# GSM-Board.net
KiCad netlist of a schematic drawn in Altium Designer
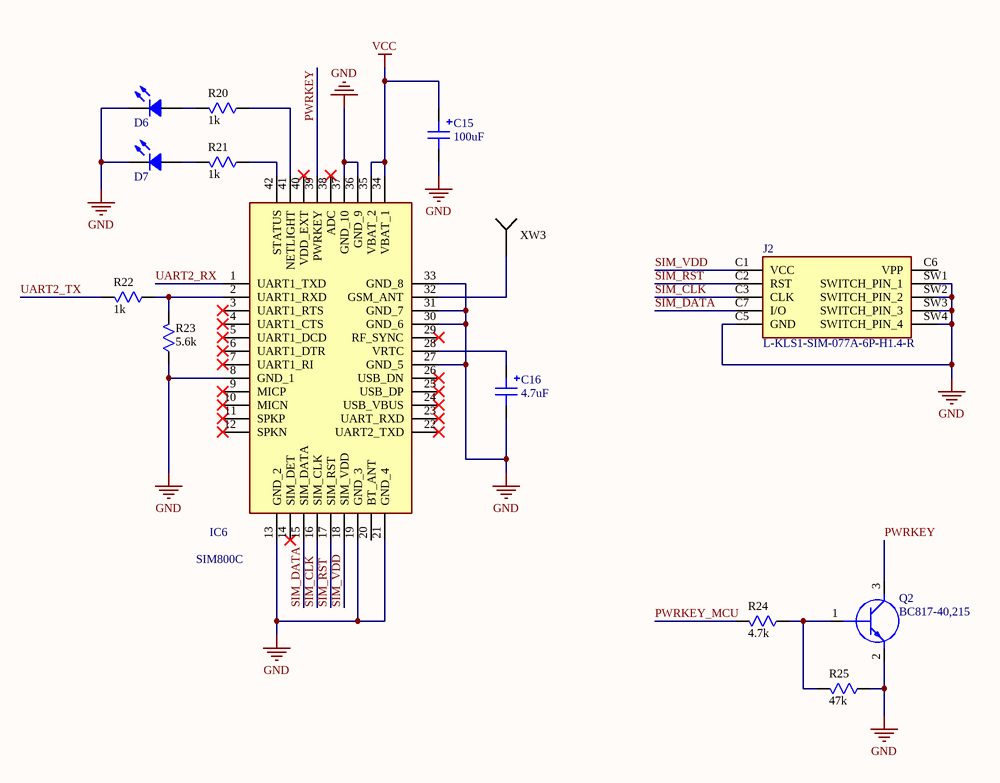
[diagram p0: GSM-Board.SchDoc]

(export (version "E")
  (design (tool "Eeschema 10.0.6"))
  (components
    (comp (ref "C15")
      (value "100uF")
      (footprint "PcbLib:CAP: TANTAL-D")
      (description "SMD Capacitor Polar")
      (libsource (lib "Schlib") (part "Capacitor_polar"))
    )
    (comp (ref "C16")
      (value "4.7uF")
      (footprint "PcbLib:CAP: TANTAL-A")
      (description "SMD Capacitor Polar")
      (libsource (lib "Schlib") (part "Capacitor_polar"))
    )
    (comp (ref "D6")
      (value "~")
      (footprint "PcbLib:LED0805")
      (description "Chip LED")
      (libsource (lib "Schlib") (part "LED"))
    )
    (comp (ref "D7")
      (value "~")
      (footprint "PcbLib:LED0805")
      (description "Chip LED")
      (libsource (lib "Schlib") (part "LED"))
    )
    (comp (ref "IC6")
      (value "SIM800C")
      (footprint "PcbLib:SIM800C")
      (description "Integrated Circuit")
      (fields (field (name "MANUFACTURER_PART_NUMBER") "-SIM800C"))
      (libsource (lib "Schlib") (part "-SIM800C"))
    )
    (comp (ref "J2")
      (value "L-KLS1-SIM-077A-6P-H1.4-R")
      (footprint "LKLS1SIM077A6PH14R")
      (description "Connector")
      (libsource (lib "Schlib") (part "L-KLS1-SIM-077A-6P-H1.4-R"))
    )
    (comp (ref "Q2")
      (value "BC817-40,215")
      (footprint "PcbLib:BC81740215")
      (description "Transistor BJT NPN")
      (fields (field (name "MOUSER PART NUMBER") "771-BC817-40-T/R"))
      (libsource (lib "*") (part "BC817-40,215"))
    )
    (comp (ref "R20")
      (value "1k")
      (footprint "PcbLib:RES: 0805")
      (fields
        (field (name "MANUFACTURER") "Yageo")
        (field (name "PARTNUMBER") "RC0201JR-07100RL")
        (field (name "VALUEMANUFACTURERPARTNUMBER") "Resistor film, 1k, , 0201, 0.05W, -55...+125°C")
      )
      (libsource (lib "Schlib") (part "Resistor"))
    )
    (comp (ref "R21")
      (value "1k")
      (footprint "PcbLib:RES: 0805")
      (fields
        (field (name "MANUFACTURER") "Yageo")
        (field (name "PARTNUMBER") "RC0201JR-07100RL")
        (field (name "VALUEMANUFACTURERPARTNUMBER") "Resistor film, 1k, , 0201, 0.05W, -55...+125°C")
      )
      (libsource (lib "Schlib") (part "Resistor"))
    )
    (comp (ref "R22")
      (value "1k")
      (footprint "PcbLib:RES: 0805")
      (fields
        (field (name "MANUFACTURER") "Yageo")
        (field (name "PARTNUMBER") "RC0201JR-07100RL")
        (field (name "VALUEMANUFACTURERPARTNUMBER") "Resistor film, 1k, , 0201, 0.05W, -55...+125°C")
      )
      (libsource (lib "Schlib") (part "Resistor"))
    )
    (comp (ref "R23")
      (value "5.6k")
      (footprint "PcbLib:RES: 0805")
      (fields
        (field (name "MANUFACTURER") "Yageo")
        (field (name "PARTNUMBER") "RC0201JR-07100RL")
        (field (name "VALUEMANUFACTURERPARTNUMBER") "Resistor film, 5.6k, , 0201, 0.05W, -55...+125°C")
      )
      (libsource (lib "Schlib") (part "Resistor"))
    )
    (comp (ref "R24")
      (value "4.7k")
      (footprint "PcbLib:RES: 0805")
      (fields
        (field (name "MANUFACTURER") "Yageo")
        (field (name "PARTNUMBER") "RC0201JR-07100RL")
        (field (name "VALUEMANUFACTURERPARTNUMBER") "Resistor film, 4.7k, , 0201, 0.05W, -55...+125°C")
      )
      (libsource (lib "Schlib") (part "Resistor"))
    )
    (comp (ref "R25")
      (value "47k")
      (footprint "PcbLib:RES: 0805")
      (fields
        (field (name "MANUFACTURER") "Yageo")
        (field (name "PARTNUMBER") "RC0201JR-07100RL")
        (field (name "VALUEMANUFACTURERPARTNUMBER") "Resistor film, 47k, , 0201, 0.05W, -55...+125°C")
      )
      (libsource (lib "Schlib") (part "Resistor"))
    )
    (comp (ref "XW3")
      (value "~")
      (footprint "CON: SMA EDGE MOUNT")
      (libsource (lib "Schlib") (part "Connector RF"))
    )
  )
  (nets
    (net (code "1") (name "/PWRKEY") (class "Default")
      (node (ref "IC6") (pin "39") (pinfunction "PWRKEY_39") (pintype "passive"))
      (node (ref "Q2") (pin "3") (pinfunction "C_3") (pintype "passive"))
    )
    (net (code "2") (name "/PWRKEY_MCU") (class "Default")
      (node (ref "R24") (pin "2") (pinfunction "2_2") (pintype "passive"))
    )
    (net (code "3") (name "/SIM_CLK") (class "Default")
      (node (ref "IC6") (pin "16") (pinfunction "SIM_CLK_16") (pintype "passive"))
      (node (ref "J2") (pin "C3") (pinfunction "CLK_C3") (pintype "passive"))
    )
    (net (code "4") (name "/SIM_DATA") (class "Default")
      (node (ref "IC6") (pin "15") (pinfunction "SIM_DATA_15") (pintype "passive"))
      (node (ref "J2") (pin "C7") (pinfunction "I/O_C7") (pintype "passive"))
    )
    (net (code "5") (name "/SIM_RST") (class "Default")
      (node (ref "IC6") (pin "17") (pinfunction "SIM_RST_17") (pintype "passive"))
      (node (ref "J2") (pin "C2") (pinfunction "RST_C2") (pintype "passive"))
    )
    (net (code "6") (name "/SIM_VDD") (class "Default")
      (node (ref "IC6") (pin "18") (pinfunction "SIM_VDD_18") (pintype "passive"))
      (node (ref "J2") (pin "C1") (pinfunction "VCC_C1") (pintype "passive"))
    )
    (net (code "7") (name "/UART2_RX") (class "Default")
      (node (ref "IC6") (pin "1") (pinfunction "UART1_TXD_1") (pintype "passive"))
    )
    (net (code "8") (name "/UART2_TX") (class "Default")
      (node (ref "R22") (pin "2") (pinfunction "2_2") (pintype "passive"))
    )
    (net (code "9") (name "GND") (class "Default")
      (node (ref "C15") (pin "2") (pinfunction "2_2") (pintype "passive"))
      (node (ref "C16") (pin "2") (pinfunction "2_2") (pintype "passive"))
      (node (ref "D6") (pin "2") (pinfunction "2_2") (pintype "passive"))
      (node (ref "D7") (pin "2") (pinfunction "2_2") (pintype "passive"))
      (node (ref "IC6") (pin "13") (pinfunction "GND_2_13") (pintype "passive"))
      (node (ref "IC6") (pin "19") (pinfunction "GND_3_19") (pintype "passive"))
      (node (ref "IC6") (pin "21") (pinfunction "GND_4_21") (pintype "passive"))
      (node (ref "IC6") (pin "27") (pinfunction "GND_5_27") (pintype "passive"))
      (node (ref "IC6") (pin "30") (pinfunction "GND_6_30") (pintype "passive"))
      (node (ref "IC6") (pin "31") (pinfunction "GND_7_31") (pintype "passive"))
      (node (ref "IC6") (pin "33") (pinfunction "GND_8_33") (pintype "passive"))
      (node (ref "IC6") (pin "36") (pinfunction "GND_9_36") (pintype "passive"))
      (node (ref "IC6") (pin "37") (pinfunction "GND_10_37") (pintype "passive"))
      (node (ref "IC6") (pin "8") (pinfunction "GND_1_8") (pintype "passive"))
      (node (ref "J2") (pin "C5") (pinfunction "GND_C5") (pintype "passive"))
      (node (ref "J2") (pin "SW1") (pinfunction "SWITCH_PIN_1_SW1") (pintype "passive"))
      (node (ref "J2") (pin "SW2") (pinfunction "SWITCH_PIN_2_SW2") (pintype "passive"))
      (node (ref "J2") (pin "SW3") (pinfunction "SWITCH_PIN_3_SW3") (pintype "passive"))
      (node (ref "J2") (pin "SW4") (pinfunction "SWITCH_PIN_4_SW4") (pintype "passive"))
      (node (ref "Q2") (pin "2") (pinfunction "E_2") (pintype "passive"))
      (node (ref "R23") (pin "1") (pinfunction "1_1") (pintype "passive"))
      (node (ref "R25") (pin "1") (pinfunction "1_1") (pintype "passive"))
    )
    (net (code "10") (name "Net-(D6-Pad1)") (class "Default")
      (node (ref "D6") (pin "1") (pinfunction "1_1") (pintype "passive"))
      (node (ref "R20") (pin "2") (pinfunction "2_2") (pintype "passive"))
    )
    (net (code "11") (name "Net-(D7-Pad1)") (class "Default")
      (node (ref "D7") (pin "1") (pinfunction "1_1") (pintype "passive"))
      (node (ref "R21") (pin "2") (pinfunction "2_2") (pintype "passive"))
    )
    (net (code "12") (name "Net-(IC6-GSM_ANT)") (class "Default")
      (node (ref "IC6") (pin "32") (pinfunction "GSM_ANT_32") (pintype "passive"))
      (node (ref "XW3") (pin "1") (pinfunction "SIG_1") (pintype "passive"))
    )
    (net (code "13") (name "Net-(IC6-NETLIGHT)") (class "Default")
      (node (ref "IC6") (pin "41") (pinfunction "NETLIGHT_41") (pintype "passive"))
      (node (ref "R20") (pin "1") (pinfunction "1_1") (pintype "passive"))
    )
    (net (code "14") (name "Net-(IC6-STATUS)") (class "Default")
      (node (ref "IC6") (pin "42") (pinfunction "STATUS_42") (pintype "passive"))
      (node (ref "R21") (pin "1") (pinfunction "1_1") (pintype "passive"))
    )
    (net (code "15") (name "Net-(IC6-UART1_RXD)") (class "Default")
      (node (ref "IC6") (pin "2") (pinfunction "UART1_RXD_2") (pintype "passive"))
      (node (ref "R22") (pin "1") (pinfunction "1_1") (pintype "passive"))
      (node (ref "R23") (pin "2") (pinfunction "2_2") (pintype "passive"))
    )
    (net (code "16") (name "Net-(IC6-VRTC)") (class "Default")
      (node (ref "C16") (pin "1") (pinfunction "1_1") (pintype "passive"))
      (node (ref "IC6") (pin "28") (pinfunction "VRTC_28") (pintype "passive"))
    )
    (net (code "17") (name "Net-(Q2-B)") (class "Default")
      (node (ref "Q2") (pin "1") (pinfunction "B_1") (pintype "passive"))
      (node (ref "R24") (pin "1") (pinfunction "1_1") (pintype "passive"))
      (node (ref "R25") (pin "2") (pinfunction "2_2") (pintype "passive"))
    )
    (net (code "18") (name "VCC") (class "Default")
      (node (ref "C15") (pin "1") (pinfunction "1_1") (pintype "passive"))
      (node (ref "IC6") (pin "34") (pinfunction "VBAT_1_34") (pintype "passive"))
      (node (ref "IC6") (pin "35") (pinfunction "VBAT_2_35") (pintype "passive"))
    )
    (net (code "19") (name "unconnected-(IC6-ADC-Pad38)") (class "Default")
      (node (ref "IC6") (pin "38") (pinfunction "ADC_38") (pintype "passive+no_connect"))
    )
    (net (code "20") (name "unconnected-(IC6-BT_ANT-Pad20)") (class "Default")
      (node (ref "IC6") (pin "20") (pinfunction "BT_ANT_20") (pintype "passive"))
    )
    (net (code "21") (name "unconnected-(IC6-MICN-Pad10)") (class "Default")
      (node (ref "IC6") (pin "10") (pinfunction "MICN_10") (pintype "passive+no_connect"))
    )
    (net (code "22") (name "unconnected-(IC6-MICP-Pad9)") (class "Default")
      (node (ref "IC6") (pin "9") (pinfunction "MICP_9") (pintype "passive+no_connect"))
    )
    (net (code "23") (name "unconnected-(IC6-RF_SYNC-Pad29)") (class "Default")
      (node (ref "IC6") (pin "29") (pinfunction "RF_SYNC_29") (pintype "passive+no_connect"))
    )
    (net (code "24") (name "unconnected-(IC6-SIM_DET-Pad14)") (class "Default")
      (node (ref "IC6") (pin "14") (pinfunction "SIM_DET_14") (pintype "passive+no_connect"))
    )
    (net (code "25") (name "unconnected-(IC6-SPKN-Pad12)") (class "Default")
      (node (ref "IC6") (pin "12") (pinfunction "SPKN_12") (pintype "passive+no_connect"))
    )
    (net (code "26") (name "unconnected-(IC6-SPKP-Pad11)") (class "Default")
      (node (ref "IC6") (pin "11") (pinfunction "SPKP_11") (pintype "passive+no_connect"))
    )
    (net (code "27") (name "unconnected-(IC6-UART1_CTS-Pad4)") (class "Default")
      (node (ref "IC6") (pin "4") (pinfunction "UART1_CTS_4") (pintype "passive+no_connect"))
    )
    (net (code "28") (name "unconnected-(IC6-UART1_DCD-Pad5)") (class "Default")
      (node (ref "IC6") (pin "5") (pinfunction "UART1_DCD_5") (pintype "passive+no_connect"))
    )
    (net (code "29") (name "unconnected-(IC6-UART1_DTR-Pad6)") (class "Default")
      (node (ref "IC6") (pin "6") (pinfunction "UART1_DTR_6") (pintype "passive+no_connect"))
    )
    (net (code "30") (name "unconnected-(IC6-UART1_RI-Pad7)") (class "Default")
      (node (ref "IC6") (pin "7") (pinfunction "UART1_RI_7") (pintype "passive+no_connect"))
    )
    (net (code "31") (name "unconnected-(IC6-UART1_RTS-Pad3)") (class "Default")
      (node (ref "IC6") (pin "3") (pinfunction "UART1_RTS_3") (pintype "passive+no_connect"))
    )
    (net (code "32") (name "unconnected-(IC6-UART2_TXD-Pad22)") (class "Default")
      (node (ref "IC6") (pin "22") (pinfunction "UART2_TXD_22") (pintype "passive+no_connect"))
    )
    (net (code "33") (name "unconnected-(IC6-UART_RXD-Pad23)") (class "Default")
      (node (ref "IC6") (pin "23") (pinfunction "UART_RXD_23") (pintype "passive+no_connect"))
    )
    (net (code "34") (name "unconnected-(IC6-USB_DN-Pad26)") (class "Default")
      (node (ref "IC6") (pin "26") (pinfunction "USB_DN_26") (pintype "passive+no_connect"))
    )
    (net (code "35") (name "unconnected-(IC6-USB_DP-Pad25)") (class "Default")
      (node (ref "IC6") (pin "25") (pinfunction "USB_DP_25") (pintype "passive+no_connect"))
    )
    (net (code "36") (name "unconnected-(IC6-USB_VBUS-Pad24)") (class "Default")
      (node (ref "IC6") (pin "24") (pinfunction "USB_VBUS_24") (pintype "passive+no_connect"))
    )
    (net (code "37") (name "unconnected-(IC6-VDD_EXT-Pad40)") (class "Default")
      (node (ref "IC6") (pin "40") (pinfunction "VDD_EXT_40") (pintype "passive+no_connect"))
    )
    (net (code "38") (name "unconnected-(J2-VPP-PadC6)") (class "Default")
      (node (ref "J2") (pin "C6") (pinfunction "VPP_C6") (pintype "passive"))
    )
  )
)
